# HK32L08x-EVAL.net
KiCad netlist of a schematic drawn in Altium Designer
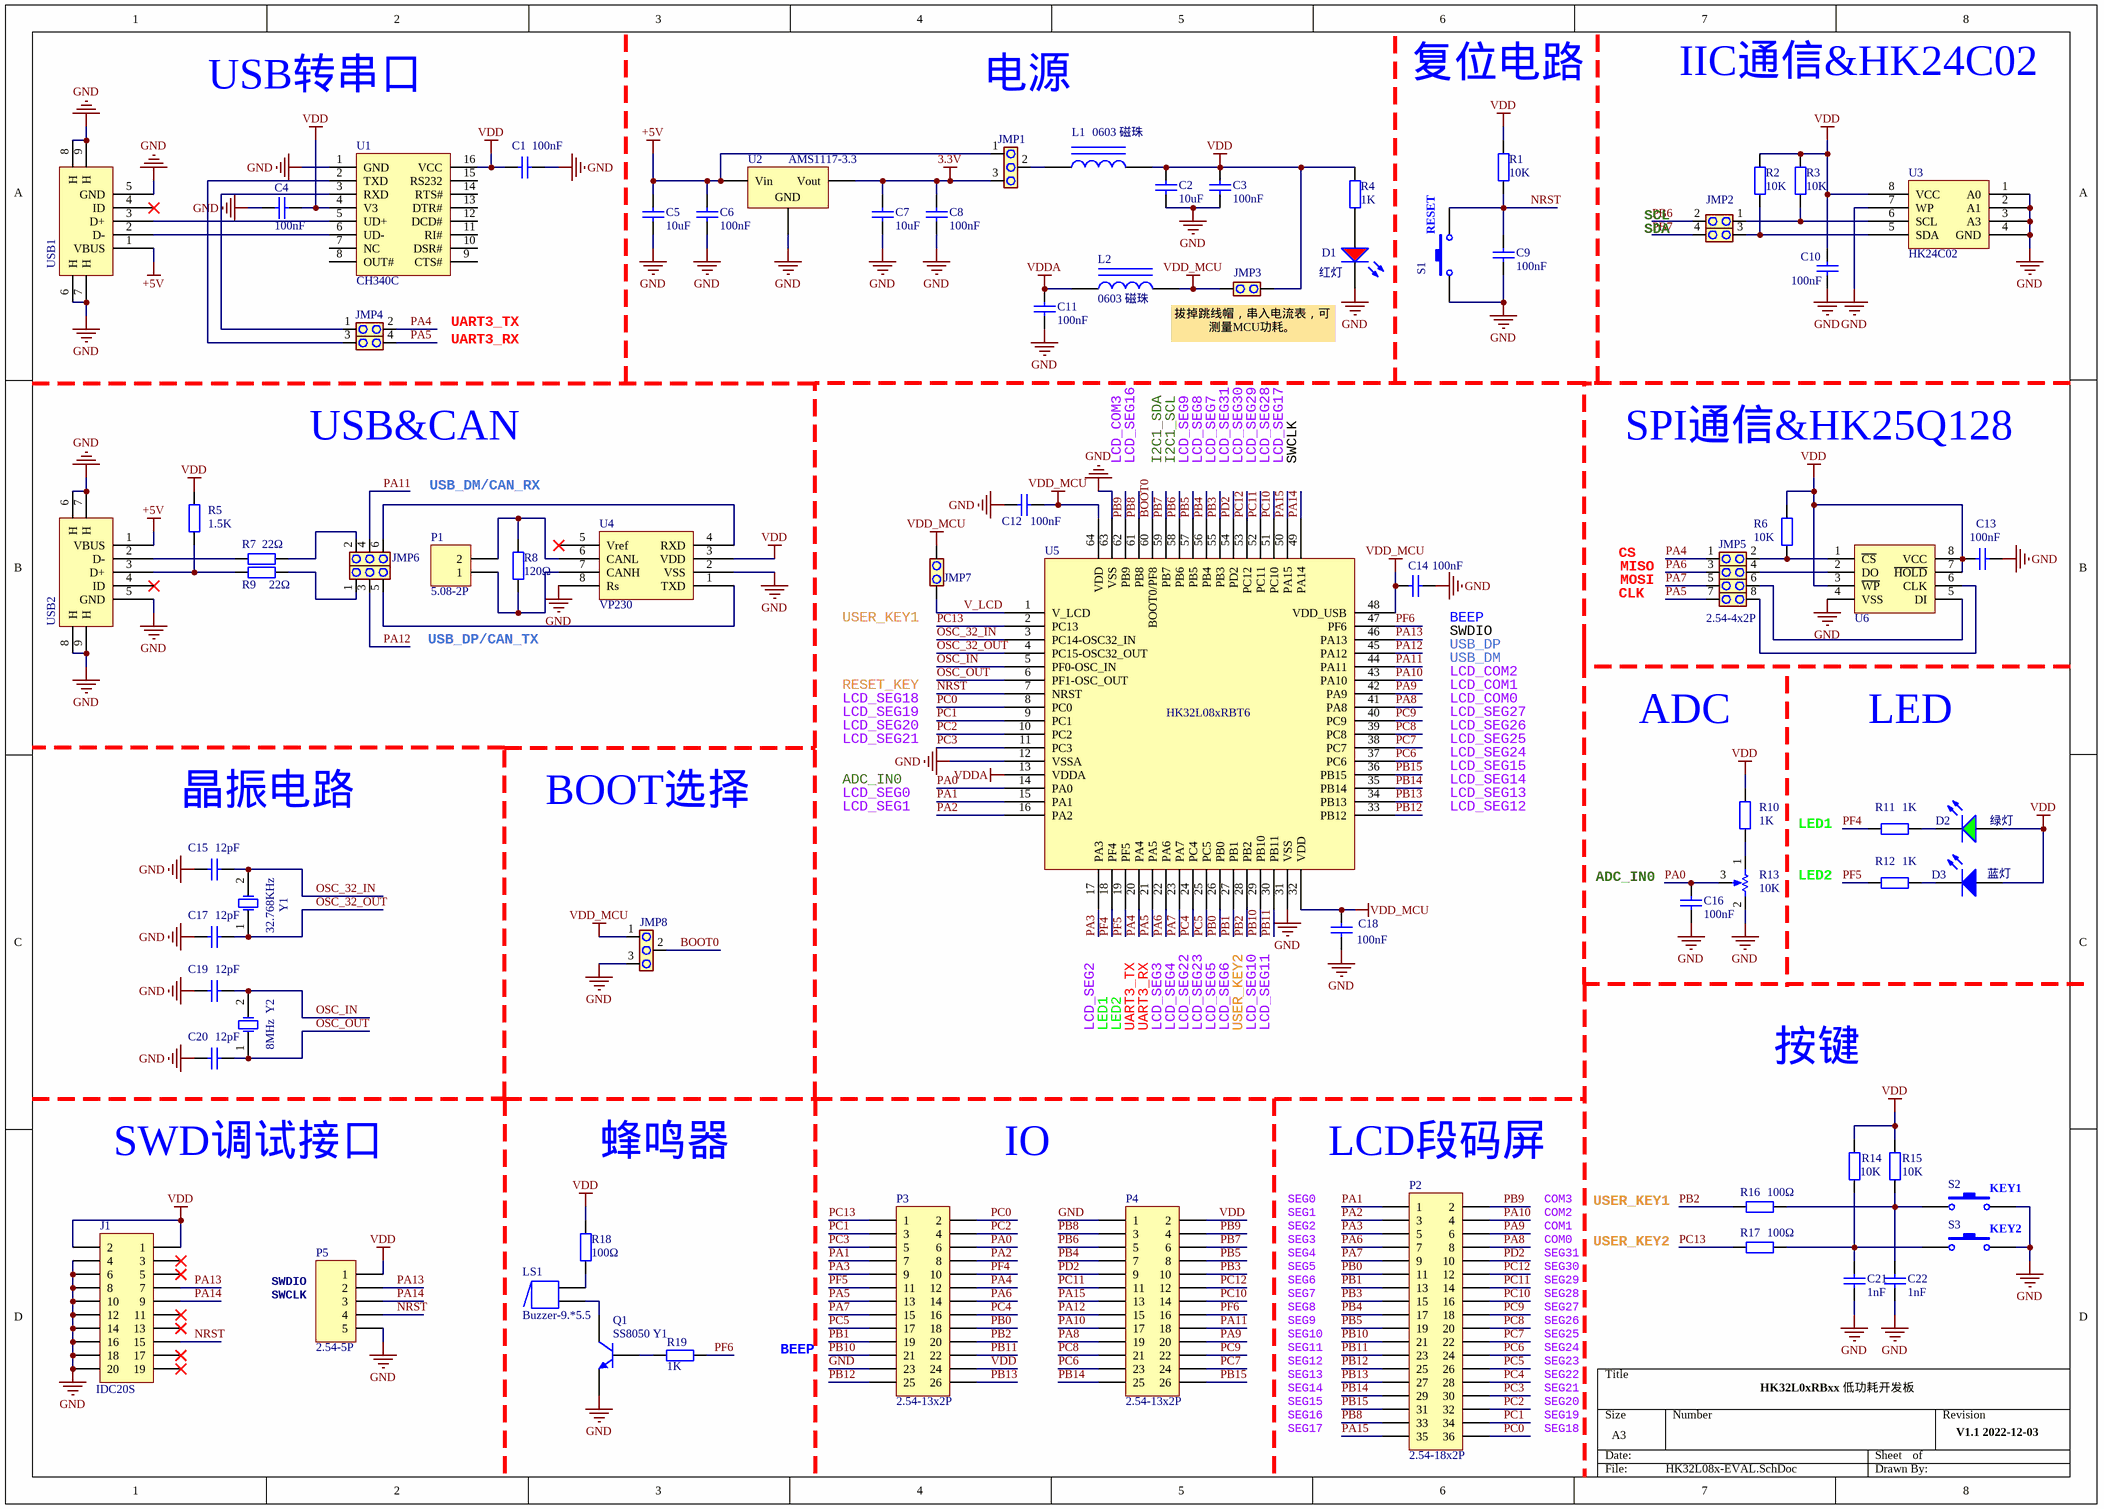
[diagram p0: HK32L08x-EVAL.SchDoc]

(export (version "E")
  (design (tool "Eeschema 10.0.6"))
  (components
    (comp (ref "C1")
      (value "100nF")
      (footprint "LC-0603_C")
      (description "贴片电容")
      (libsource (lib "Miscellaneous Devices LC") (part "0603 100nF (104) 10% 50V"))
    )
    (comp (ref "C2")
      (value "10uF")
      (footprint "LC-0603_C")
      (description "贴片电容")
      (libsource (lib "Miscellaneous Devices LC") (part "0603 10uF (106) 10% 10V"))
    )
    (comp (ref "C3")
      (value "100nF")
      (footprint "LC-0603_C")
      (description "贴片电容")
      (libsource (lib "Miscellaneous Devices LC") (part "0603 100nF (104) 10% 50V"))
    )
    (comp (ref "C4")
      (value "100nF")
      (footprint "LC-0603_C")
      (description "贴片电容")
      (libsource (lib "Miscellaneous Devices LC") (part "0603 100nF (104) 10% 50V"))
    )
    (comp (ref "C5")
      (value "10uF")
      (footprint "LC-1206_C")
      (description "贴片电容")
      (libsource (lib "Miscellaneous Devices LC") (part "1206 10uF (106) 10% 50V"))
    )
    (comp (ref "C6")
      (value "100nF")
      (footprint "LC-0603_C")
      (description "贴片电容")
      (libsource (lib "Miscellaneous Devices LC") (part "0603 100nF (104) 10% 50V"))
    )
    (comp (ref "C7")
      (value "10uF")
      (footprint "LC-1206_C")
      (description "贴片电容")
      (libsource (lib "Miscellaneous Devices LC") (part "1206 10uF (106) 10% 50V"))
    )
    (comp (ref "C8")
      (value "100nF")
      (footprint "LC-0603_C")
      (description "贴片电容")
      (libsource (lib "Miscellaneous Devices LC") (part "0603 100nF (104) 10% 50V"))
    )
    (comp (ref "C9")
      (value "100nF")
      (footprint "LC-0603_C")
      (description "贴片电容")
      (libsource (lib "Miscellaneous Devices LC") (part "0603 100nF (104) 10% 50V"))
    )
    (comp (ref "C10")
      (value "100nF")
      (footprint "LC-0603_C")
      (description "贴片电容")
      (libsource (lib "Miscellaneous Devices LC") (part "0603 100nF (104) 10% 50V"))
    )
    (comp (ref "C11")
      (value "100nF")
      (footprint "LC-0603_C")
      (description "贴片电容")
      (libsource (lib "Miscellaneous Devices LC") (part "0603 100nF (104) 10% 50V"))
    )
    (comp (ref "C12")
      (value "100nF")
      (footprint "LC-0603_C")
      (description "贴片电容")
      (libsource (lib "Miscellaneous Devices LC") (part "0603 100nF (104) 10% 50V"))
    )
    (comp (ref "C13")
      (value "100nF")
      (footprint "LC-0603_C")
      (description "贴片电容")
      (libsource (lib "Miscellaneous Devices LC") (part "0603 100nF (104) 10% 50V"))
    )
    (comp (ref "C14")
      (value "100nF")
      (footprint "LC-0603_C")
      (description "贴片电容")
      (libsource (lib "Miscellaneous Devices LC") (part "0603 100nF (104) 10% 50V"))
    )
    (comp (ref "C15")
      (value "12pF")
      (footprint "LC-0603_C")
      (description "贴片电容")
      (libsource (lib "Miscellaneous Devices LC") (part "0603 12pF (120) 5% 50V"))
    )
    (comp (ref "C16")
      (value "100nF")
      (footprint "LC-0603_C")
      (description "贴片电容")
      (libsource (lib "Miscellaneous Devices LC") (part "0603 100nF (104) 10% 50V"))
    )
    (comp (ref "C17")
      (value "12pF")
      (footprint "LC-0603_C")
      (description "贴片电容")
      (libsource (lib "Miscellaneous Devices LC") (part "0603 12pF (120) 5% 50V"))
    )
    (comp (ref "C18")
      (value "100nF")
      (footprint "LC-0603_C")
      (description "贴片电容")
      (libsource (lib "Miscellaneous Devices LC") (part "0603 100nF (104) 10% 50V"))
    )
    (comp (ref "C19")
      (value "12pF")
      (footprint "LC-0603_C")
      (description "贴片电容")
      (libsource (lib "Miscellaneous Devices LC") (part "0603 12pF (120) 5% 50V"))
    )
    (comp (ref "C20")
      (value "12pF")
      (footprint "LC-0603_C")
      (description "贴片电容")
      (libsource (lib "Miscellaneous Devices LC") (part "0603 12pF (120) 5% 50V"))
    )
    (comp (ref "C21")
      (value "1nF")
      (footprint "LC-0603_C")
      (description "贴片电容")
      (libsource (lib "Miscellaneous Devices LC") (part "0603 1nF (102) 10% 50V"))
    )
    (comp (ref "C22")
      (value "1nF")
      (footprint "LC-0603_C")
      (description "贴片电容")
      (libsource (lib "Miscellaneous Devices LC") (part "0603 1nF (102) 10% 50V"))
    )
    (comp (ref "D1")
      (value "红灯")
      (footprint "LC-0603_LED_S1")
      (description "贴片LED")
      (libsource (lib "Miscellaneous Devices LC") (part "0603 红灯"))
    )
    (comp (ref "D2")
      (value "绿灯")
      (footprint "LC-0603_LED_S1")
      (description "贴片LED")
      (libsource (lib "Miscellaneous Devices LC") (part "0603 绿灯"))
    )
    (comp (ref "D3")
      (value "蓝灯")
      (footprint "LC-0603_LED_S1")
      (description "贴片LED")
      (libsource (lib "Miscellaneous Devices LC") (part "0603 蓝灯"))
    )
    (comp (ref "J1")
      (value "IDC20S")
      (footprint "JTAG20P")
      (description "接插件")
      (fields (field (name "PUBLISHER") "Altium Limited"))
      (libsource (lib "Miscellaneous Connectors") (part "Header 10X2H"))
    )
    (comp (ref "JMP1")
      (value "2.54-3P")
      (footprint "HDR1X3")
      (description "排针")
      (libsource (lib "HK32L08x-EVAL") (part "JMP-3P"))
    )
    (comp (ref "JMP2")
      (value "2.54-2x2P")
      (footprint "HDR2X2")
      (description "排针")
      (libsource (lib "HK32L08x-EVAL") (part "JMP-2-2P"))
    )
    (comp (ref "JMP3")
      (value "2.54-2x1")
      (footprint "HDR1X2")
      (description "排针")
      (libsource (lib "HK32L08x-EVAL") (part "JMP-2P"))
    )
    (comp (ref "JMP4")
      (value "2.54-2x2P")
      (footprint "HDR2X2")
      (description "排针")
      (libsource (lib "") (part "JMP-2-2P_1"))
    )
    (comp (ref "JMP5")
      (value "2.54-4x2P")
      (footprint "HDR2X4")
      (description "排针")
      (libsource (lib "HK32L08x-EVAL") (part "JMP-2x4P"))
    )
    (comp (ref "JMP6")
      (value "2.54-3x2P")
      (footprint "HDR2X3")
      (description "排针")
      (libsource (lib "HK32L08x-EVAL") (part "JMP-2x3P"))
    )
    (comp (ref "JMP7")
      (value "2.54-2P")
      (footprint "HDR1X2")
      (description "排针")
      (libsource (lib "") (part "JMP-2P_1"))
    )
    (comp (ref "JMP8")
      (value "2.54-3P")
      (footprint "HDR1X3")
      (description "排针")
      (libsource (lib "HK32L08x-EVAL") (part "JMP-3P"))
    )
    (comp (ref "L1")
      (value "0603 磁珠")
      (footprint "LC-0603_L")
      (description "贴片电感")
      (libsource (lib "") (part "0603 10uH 10%_1"))
    )
    (comp (ref "L2")
      (value "0603 磁珠")
      (footprint "LC-0603_L")
      (description "贴片电感")
      (libsource (lib "Miscellaneous Devices LC") (part "0603 10uH 10%"))
    )
    (comp (ref "LS1")
      (value "Buzzer-9.*5.5")
      (footprint "Buzzer-2P-9x5.5")
      (description "直插蜂鸣器")
      (fields (field (name "PUBLISHER") "Altium Limited"))
      (libsource (lib "Miscellaneous Devices") (part "Buzzer"))
    )
    (comp (ref "P1")
      (value "5.08-2P")
      (footprint "HD-2PIN-5.08")
      (description "接插件")
      (fields (field (name "PUBLISHER") "Altium Limited"))
      (libsource (lib "Miscellaneous Connectors") (part "Header 2"))
    )
    (comp (ref "P2")
      (value "2.54-18x2P")
      (footprint "LCD128_2x18-2.54")
      (description "排母")
      (fields (field (name "PUBLISHER") "Altium Limited"))
      (libsource (lib "Miscellaneous Connectors") (part "Header 18X2"))
    )
    (comp (ref "P3")
      (value "2.54-13x2P")
      (footprint "HDR2X13")
      (description "排针")
      (fields (field (name "PUBLISHER") "Altium Limited"))
      (libsource (lib "Miscellaneous Connectors") (part "Header 13X2"))
    )
    (comp (ref "P4")
      (value "2.54-13x2P")
      (footprint "HDR2X13")
      (description "排针")
      (fields (field (name "PUBLISHER") "Altium Limited"))
      (libsource (lib "Miscellaneous Connectors") (part "Header 13X2"))
    )
    (comp (ref "P5")
      (value "2.54-5P")
      (footprint "HDR1X5")
      (description "排针")
      (fields (field (name "PUBLISHER") "Altium Limited"))
      (libsource (lib "Miscellaneous Connectors") (part "Header 5"))
    )
    (comp (ref "Q1")
      (value "SS8050 Y1")
      (footprint "LC-SOT-23(SOT-23-3)")
      (description "贴片三极管")
      (libsource (lib "Transistor_NPN") (part "SOT-23 SS8050 Y1"))
    )
    (comp (ref "R1")
      (value "10K")
      (footprint "LC-0603_R")
      (description "贴片电阻")
      (libsource (lib "") (part "0603 10KΩ (1002) 1%_1"))
    )
    (comp (ref "R2")
      (value "10K")
      (footprint "LC-0603_R")
      (description "贴片电阻")
      (libsource (lib "Miscellaneous Devices LC") (part "0603 10KΩ (1002) 1%"))
    )
    (comp (ref "R3")
      (value "10K")
      (footprint "LC-0603_R")
      (description "贴片电阻")
      (libsource (lib "Miscellaneous Devices LC") (part "0603 10KΩ (1002) 1%"))
    )
    (comp (ref "R4")
      (value "1K")
      (footprint "LC-0603_R")
      (description "贴片电阻")
      (libsource (lib "Miscellaneous Devices LC") (part "0603 1KΩ (1001) 1%"))
    )
    (comp (ref "R5")
      (value "1.5K")
      (footprint "LC-0603_R")
      (description "贴片电阻")
      (libsource (lib "Miscellaneous Devices LC") (part "0603 1.5KΩ (1501) 1%"))
    )
    (comp (ref "R6")
      (value "10K")
      (footprint "LC-0603_R")
      (description "贴片电阻")
      (libsource (lib "") (part "0603 10KΩ (1002) 1%_1"))
    )
    (comp (ref "R7")
      (value "22Ω")
      (footprint "LC-0603_R")
      (description "贴片电阻")
      (libsource (lib "Miscellaneous Devices LC") (part "0603 22Ω (22R0) 1%"))
    )
    (comp (ref "R8")
      (value "120Ω")
      (footprint "LC-0603_R")
      (description "贴片电阻")
      (libsource (lib "Miscellaneous Devices LC") (part "0603 120Ω (1200) 1%"))
    )
    (comp (ref "R9")
      (value "22Ω")
      (footprint "LC-0603_R")
      (description "贴片电阻")
      (libsource (lib "Miscellaneous Devices LC") (part "0603 22Ω (22R0) 1%"))
    )
    (comp (ref "R10")
      (value "1K")
      (footprint "LC-0603_R")
      (description "贴片电阻")
      (libsource (lib "Miscellaneous Devices LC") (part "0603 1KΩ (1001) 1%"))
    )
    (comp (ref "R11")
      (value "1K")
      (footprint "LC-0603_R")
      (description "贴片电阻")
      (libsource (lib "") (part "0603 1KΩ (1001) 1%_1"))
    )
    (comp (ref "R12")
      (value "1K")
      (footprint "LC-0603_R")
      (description "贴片电阻")
      (libsource (lib "") (part "0603 1KΩ (1001) 1%_1"))
    )
    (comp (ref "R13")
      (value "10K")
      (footprint "VR-3P")
      (description "直插电位器")
      (fields (field (name "Comment") "3386P-1") (field (name "PUBLISHER") "Altium Limited"))
      (libsource (lib "Miscellaneous Devices") (part "RPot"))
    )
    (comp (ref "R14")
      (value "10K")
      (footprint "LC-0603_R")
      (description "贴片电阻")
      (libsource (lib "") (part "0603 10KΩ (1002) 1%_1"))
    )
    (comp (ref "R15")
      (value "10K")
      (footprint "LC-0603_R")
      (description "贴片电阻")
      (libsource (lib "") (part "0603 10KΩ (1002) 1%_1"))
    )
    (comp (ref "R16")
      (value "100Ω")
      (footprint "LC-0603_R")
      (description "贴片电阻")
      (libsource (lib "Miscellaneous Devices LC") (part "0603 100Ω (1000) 1%"))
    )
    (comp (ref "R17")
      (value "100Ω")
      (footprint "LC-0603_R")
      (description "贴片电阻")
      (libsource (lib "Miscellaneous Devices LC") (part "0603 100Ω (1000) 1%"))
    )
    (comp (ref "R18")
      (value "100Ω")
      (footprint "LC-0603_R")
      (description "贴片电阻")
      (libsource (lib "Miscellaneous Devices LC") (part "0603 100Ω (1000) 1%"))
    )
    (comp (ref "R19")
      (value "1K")
      (footprint "LC-0603_R")
      (description "贴片电阻")
      (libsource (lib "") (part "0603 1KΩ (1001) 1%_2"))
    )
    (comp (ref "S1")
      (value "KEY-3*6*2.5")
      (footprint "SMD_KEY-2P")
      (description "贴片按键")
      (fields (field (name "PUBLISHER") "Altium Limited"))
      (libsource (lib "Miscellaneous Devices") (part "SW-PB"))
    )
    (comp (ref "S2")
      (value "KEY-3*6*2.5")
      (footprint "SMD_KEY-2P")
      (description "贴片按键")
      (fields (field (name "PUBLISHER") "Altium Limited"))
      (libsource (lib "Miscellaneous Devices") (part "SW-PB"))
    )
    (comp (ref "S3")
      (value "KEY-3*6*2.5")
      (footprint "SMD_KEY-2P")
      (description "贴片按键")
      (fields (field (name "PUBLISHER") "Altium Limited"))
      (libsource (lib "Miscellaneous Devices") (part "SW-PB"))
    )
    (comp (ref "U1")
      (value "CH340C")
      (footprint "LC-SOIC-16_150mil")
      (description "贴片IC")
      (libsource (lib "HK32L08x-EVAL") (part "CH340C"))
    )
    (comp (ref "U2")
      (value "AMS1117-3.3")
      (footprint "LC-SOT-223")
      (description "贴片IC")
      (libsource (lib "Miscellaneous Devices LC") (part "SOT-223 AMS1117-3.3"))
    )
    (comp (ref "U3")
      (value "HK24C02")
      (footprint "LC-SOIC-8_150mil")
      (description "贴片IC")
      (libsource (lib "IC") (part "EEPROM/AT24C256C-SSHL-T"))
    )
    (comp (ref "U4")
      (value "VP230")
      (footprint "LC-SOIC-8_150mil")
      (description "贴片IC")
      (libsource (lib "HK32L08x-EVAL") (part "VP230"))
    )
    (comp (ref "U5")
      (value "HK32L08xRBT6")
      (footprint "LC-LQFP-64_10x10x05P")
      (description "贴片IC")
      (libsource (lib "HK32L08x-EVAL") (part "HK32L08xRBT6"))
    )
    (comp (ref "U6")
      (value "HK25Q128")
      (footprint "FLASH-SOP8L")
      (description "贴片IC")
      (libsource (lib "HK32L08x-EVAL") (part "HK25Q128"))
    )
    (comp (ref "USB1")
      (value "MINI-USB")
      (footprint "mini_USB")
      (description "接插件")
      (libsource (lib "HK32L08x-EVAL") (part "MINI-USB"))
    )
    (comp (ref "USB2")
      (value "MINI-USB")
      (footprint "mini_USB")
      (description "接插件")
      (libsource (lib "") (part "MINI-USB_1"))
    )
    (comp (ref "Y1")
      (value "32.768KHz")
      (footprint "JZ32768")
      (description "直插晶振")
      (libsource (lib "Miscellaneous Devices LC") (part "SMD-3215_2P 32.768KHz 20ppm 12.5pF"))
    )
    (comp (ref "Y2")
      (value "8MHz")
      (footprint "JZ49S")
      (description "直插晶振")
      (libsource (lib "Miscellaneous Devices LC") (part "SMD-5032_2P 8MHz 20ppm 20pF"))
    )
  )
  (nets
    (net (code "1") (name "+5V") (class "Default")
      (node (ref "C5") (pin "2") (pinfunction "2_2") (pintype "passive"))
      (node (ref "C6") (pin "2") (pinfunction "2_2") (pintype "passive"))
      (node (ref "JMP1") (pin "1") (pinfunction "1_1") (pintype "passive"))
      (node (ref "U2") (pin "3") (pinfunction "Vin_3") (pintype "passive"))
      (node (ref "USB1") (pin "1") (pinfunction "VBUS_1") (pintype "passive"))
      (node (ref "USB2") (pin "1") (pinfunction "VBUS_1") (pintype "passive"))
    )
    (net (code "2") (name "/BOOT0") (class "Default")
      (node (ref "JMP8") (pin "2") (pinfunction "2_2") (pintype "passive"))
      (node (ref "U5") (pin "60") (pinfunction "BOOT0/PF8_60") (pintype "passive"))
    )
    (net (code "3") (name "/NRST") (class "Default")
      (node (ref "C9") (pin "2") (pinfunction "2_2") (pintype "passive"))
      (node (ref "J1") (pin "15") (pinfunction "15_15") (pintype "passive"))
      (node (ref "P5") (pin "4") (pinfunction "4_4") (pintype "passive"))
      (node (ref "R1") (pin "1") (pinfunction "1_1") (pintype "passive"))
      (node (ref "S1") (pin "2") (pinfunction "2_2") (pintype "passive"))
      (node (ref "U5") (pin "7") (pinfunction "NRST_7") (pintype "passive"))
    )
    (net (code "4") (name "/OSC_32_IN") (class "Default")
      (node (ref "C15") (pin "2") (pinfunction "2_2") (pintype "passive"))
      (node (ref "U5") (pin "3") (pinfunction "PC14-OSC32_IN_3") (pintype "passive"))
      (node (ref "Y1") (pin "2") (pinfunction "OSC2_2") (pintype "passive"))
    )
    (net (code "5") (name "/OSC_32_OUT") (class "Default")
      (node (ref "C17") (pin "2") (pinfunction "2_2") (pintype "passive"))
      (node (ref "U5") (pin "4") (pinfunction "PC15-OSC32_OUT_4") (pintype "passive"))
      (node (ref "Y1") (pin "1") (pinfunction "OSC1_1") (pintype "passive"))
    )
    (net (code "6") (name "/OSC_IN") (class "Default")
      (node (ref "C19") (pin "2") (pinfunction "2_2") (pintype "passive"))
      (node (ref "U5") (pin "5") (pinfunction "PF0-OSC_IN_5") (pintype "passive"))
      (node (ref "Y2") (pin "2") (pinfunction "OSC2_2") (pintype "passive"))
    )
    (net (code "7") (name "/OSC_OUT") (class "Default")
      (node (ref "C20") (pin "2") (pinfunction "2_2") (pintype "passive"))
      (node (ref "U5") (pin "6") (pinfunction "PF1-OSC_OUT_6") (pintype "passive"))
      (node (ref "Y2") (pin "1") (pinfunction "OSC1_1") (pintype "passive"))
    )
    (net (code "8") (name "/PA0") (class "Default")
      (node (ref "C16") (pin "1") (pinfunction "1_1") (pintype "passive"))
      (node (ref "P3") (pin "6") (pinfunction "6_6") (pintype "passive"))
      (node (ref "R13") (pin "3") (pinfunction "TAP_3") (pintype "passive"))
      (node (ref "U5") (pin "14") (pinfunction "PA0_14") (pintype "passive"))
    )
    (net (code "9") (name "/PA1") (class "Default")
      (node (ref "P2") (pin "1") (pinfunction "1_1") (pintype "passive"))
      (node (ref "P3") (pin "7") (pinfunction "7_7") (pintype "passive"))
      (node (ref "U5") (pin "15") (pinfunction "PA1_15") (pintype "passive"))
    )
    (net (code "10") (name "/PA2") (class "Default")
      (node (ref "P2") (pin "3") (pinfunction "3_3") (pintype "passive"))
      (node (ref "P3") (pin "8") (pinfunction "8_8") (pintype "passive"))
      (node (ref "U5") (pin "16") (pinfunction "PA2_16") (pintype "passive"))
    )
    (net (code "11") (name "/PA3") (class "Default")
      (node (ref "P2") (pin "5") (pinfunction "5_5") (pintype "passive"))
      (node (ref "P3") (pin "9") (pinfunction "9_9") (pintype "passive"))
      (node (ref "U5") (pin "17") (pinfunction "PA3_17") (pintype "passive"))
    )
    (net (code "12") (name "/PA4") (class "Default")
      (node (ref "JMP4") (pin "2") (pinfunction "2_2") (pintype "passive"))
      (node (ref "JMP5") (pin "1") (pinfunction "1_1") (pintype "passive"))
      (node (ref "P3") (pin "12") (pinfunction "12_12") (pintype "passive"))
      (node (ref "U5") (pin "20") (pinfunction "PA4_20") (pintype "passive"))
    )
    (net (code "13") (name "/PA5") (class "Default")
      (node (ref "JMP4") (pin "4") (pinfunction "4_4") (pintype "passive"))
      (node (ref "JMP5") (pin "7") (pinfunction "7_7") (pintype "passive"))
      (node (ref "P3") (pin "13") (pinfunction "13_13") (pintype "passive"))
      (node (ref "U5") (pin "21") (pinfunction "PA5_21") (pintype "passive"))
    )
    (net (code "14") (name "/PA6") (class "Default")
      (node (ref "JMP5") (pin "3") (pinfunction "3_3") (pintype "passive"))
      (node (ref "P2") (pin "7") (pinfunction "7_7") (pintype "passive"))
      (node (ref "P3") (pin "14") (pinfunction "14_14") (pintype "passive"))
      (node (ref "U5") (pin "22") (pinfunction "PA6_22") (pintype "passive"))
    )
    (net (code "15") (name "/PA7") (class "Default")
      (node (ref "JMP5") (pin "5") (pinfunction "5_5") (pintype "passive"))
      (node (ref "P2") (pin "9") (pinfunction "9_9") (pintype "passive"))
      (node (ref "P3") (pin "15") (pinfunction "15_15") (pintype "passive"))
      (node (ref "U5") (pin "23") (pinfunction "PA7_23") (pintype "passive"))
    )
    (net (code "16") (name "/PA8") (class "Default")
      (node (ref "P2") (pin "8") (pinfunction "8_8") (pintype "passive"))
      (node (ref "P4") (pin "19") (pinfunction "19_19") (pintype "passive"))
      (node (ref "U5") (pin "41") (pinfunction "PA8_41") (pintype "passive"))
    )
    (net (code "17") (name "/PA9") (class "Default")
      (node (ref "P2") (pin "6") (pinfunction "6_6") (pintype "passive"))
      (node (ref "P4") (pin "20") (pinfunction "20_20") (pintype "passive"))
      (node (ref "U5") (pin "42") (pinfunction "PA9_42") (pintype "passive"))
    )
    (net (code "18") (name "/PA10") (class "Default")
      (node (ref "P2") (pin "4") (pinfunction "4_4") (pintype "passive"))
      (node (ref "P4") (pin "17") (pinfunction "17_17") (pintype "passive"))
      (node (ref "U5") (pin "43") (pinfunction "PA10_43") (pintype "passive"))
    )
    (net (code "19") (name "/PA11") (class "Default")
      (node (ref "JMP6") (pin "4") (pinfunction "4_4") (pintype "passive"))
      (node (ref "P4") (pin "18") (pinfunction "18_18") (pintype "passive"))
      (node (ref "U5") (pin "44") (pinfunction "PA11_44") (pintype "passive"))
    )
    (net (code "20") (name "/PA12") (class "Default")
      (node (ref "JMP6") (pin "3") (pinfunction "3_3") (pintype "passive"))
      (node (ref "P4") (pin "15") (pinfunction "15_15") (pintype "passive"))
      (node (ref "U5") (pin "45") (pinfunction "PA12_45") (pintype "passive"))
    )
    (net (code "21") (name "/PA13") (class "Default")
      (node (ref "J1") (pin "7") (pinfunction "7_7") (pintype "passive"))
      (node (ref "P5") (pin "2") (pinfunction "2_2") (pintype "passive"))
      (node (ref "U5") (pin "46") (pinfunction "PA13_46") (pintype "passive"))
    )
    (net (code "22") (name "/PA14") (class "Default")
      (node (ref "J1") (pin "9") (pinfunction "9_9") (pintype "passive"))
      (node (ref "P5") (pin "3") (pinfunction "3_3") (pintype "passive"))
      (node (ref "U5") (pin "49") (pinfunction "PA14_49") (pintype "passive"))
    )
    (net (code "23") (name "/PA15") (class "Default")
      (node (ref "P2") (pin "35") (pinfunction "35_35") (pintype "passive"))
      (node (ref "P4") (pin "13") (pinfunction "13_13") (pintype "passive"))
      (node (ref "U5") (pin "50") (pinfunction "PA15_50") (pintype "passive"))
    )
    (net (code "24") (name "/PB0") (class "Default")
      (node (ref "P2") (pin "11") (pinfunction "11_11") (pintype "passive"))
      (node (ref "P3") (pin "18") (pinfunction "18_18") (pintype "passive"))
      (node (ref "U5") (pin "26") (pinfunction "PB0_26") (pintype "passive"))
    )
    (net (code "25") (name "/PB1") (class "Default")
      (node (ref "P2") (pin "13") (pinfunction "13_13") (pintype "passive"))
      (node (ref "P3") (pin "19") (pinfunction "19_19") (pintype "passive"))
      (node (ref "U5") (pin "27") (pinfunction "PB1_27") (pintype "passive"))
    )
    (net (code "26") (name "/PB2") (class "Default")
      (node (ref "P3") (pin "20") (pinfunction "20_20") (pintype "passive"))
      (node (ref "R16") (pin "1") (pinfunction "1_1") (pintype "passive"))
      (node (ref "U5") (pin "28") (pinfunction "PB2_28") (pintype "passive"))
    )
    (net (code "27") (name "/PB3") (class "Default")
      (node (ref "P2") (pin "15") (pinfunction "15_15") (pintype "passive"))
      (node (ref "P4") (pin "10") (pinfunction "10_10") (pintype "passive"))
      (node (ref "U5") (pin "55") (pinfunction "PB3_55") (pintype "passive"))
    )
    (net (code "28") (name "/PB4") (class "Default")
      (node (ref "P2") (pin "17") (pinfunction "17_17") (pintype "passive"))
      (node (ref "P4") (pin "7") (pinfunction "7_7") (pintype "passive"))
      (node (ref "U5") (pin "56") (pinfunction "PB4_56") (pintype "passive"))
    )
    (net (code "29") (name "/PB5") (class "Default")
      (node (ref "P2") (pin "19") (pinfunction "19_19") (pintype "passive"))
      (node (ref "P4") (pin "8") (pinfunction "8_8") (pintype "passive"))
      (node (ref "U5") (pin "57") (pinfunction "PB5_57") (pintype "passive"))
    )
    (net (code "30") (name "/PB6") (class "Default")
      (node (ref "JMP2") (pin "2") (pinfunction "2_2") (pintype "passive"))
      (node (ref "P4") (pin "5") (pinfunction "5_5") (pintype "passive"))
      (node (ref "U5") (pin "58") (pinfunction "PB6_58") (pintype "passive"))
    )
    (net (code "31") (name "/PB7") (class "Default")
      (node (ref "JMP2") (pin "4") (pinfunction "4_4") (pintype "passive"))
      (node (ref "P4") (pin "6") (pinfunction "6_6") (pintype "passive"))
      (node (ref "U5") (pin "59") (pinfunction "PB7_59") (pintype "passive"))
    )
    (net (code "32") (name "/PB8") (class "Default")
      (node (ref "P2") (pin "33") (pinfunction "33_33") (pintype "passive"))
      (node (ref "P4") (pin "3") (pinfunction "3_3") (pintype "passive"))
      (node (ref "U5") (pin "61") (pinfunction "PB8_61") (pintype "passive"))
    )
    (net (code "33") (name "/PB9") (class "Default")
      (node (ref "P2") (pin "2") (pinfunction "2_2") (pintype "passive"))
      (node (ref "P4") (pin "4") (pinfunction "4_4") (pintype "passive"))
      (node (ref "U5") (pin "62") (pinfunction "PB9_62") (pintype "passive"))
    )
    (net (code "34") (name "/PB10") (class "Default")
      (node (ref "P2") (pin "21") (pinfunction "21_21") (pintype "passive"))
      (node (ref "P3") (pin "21") (pinfunction "21_21") (pintype "passive"))
      (node (ref "U5") (pin "29") (pinfunction "PB10_29") (pintype "passive"))
    )
    (net (code "35") (name "/PB11") (class "Default")
      (node (ref "P2") (pin "23") (pinfunction "23_23") (pintype "passive"))
      (node (ref "P3") (pin "22") (pinfunction "22_22") (pintype "passive"))
      (node (ref "U5") (pin "30") (pinfunction "PB11_30") (pintype "passive"))
    )
    (net (code "36") (name "/PB12") (class "Default")
      (node (ref "P2") (pin "25") (pinfunction "25_25") (pintype "passive"))
      (node (ref "P3") (pin "25") (pinfunction "25_25") (pintype "passive"))
      (node (ref "U5") (pin "33") (pinfunction "PB12_33") (pintype "passive"))
    )
    (net (code "37") (name "/PB13") (class "Default")
      (node (ref "P2") (pin "27") (pinfunction "27_27") (pintype "passive"))
      (node (ref "P3") (pin "26") (pinfunction "26_26") (pintype "passive"))
      (node (ref "U5") (pin "34") (pinfunction "PB13_34") (pintype "passive"))
    )
    (net (code "38") (name "/PB14") (class "Default")
      (node (ref "P2") (pin "29") (pinfunction "29_29") (pintype "passive"))
      (node (ref "P4") (pin "25") (pinfunction "25_25") (pintype "passive"))
      (node (ref "U5") (pin "35") (pinfunction "PB14_35") (pintype "passive"))
    )
    (net (code "39") (name "/PB15") (class "Default")
      (node (ref "P2") (pin "31") (pinfunction "31_31") (pintype "passive"))
      (node (ref "P4") (pin "26") (pinfunction "26_26") (pintype "passive"))
      (node (ref "U5") (pin "36") (pinfunction "PB15_36") (pintype "passive"))
    )
    (net (code "40") (name "/PC0") (class "Default")
      (node (ref "P2") (pin "36") (pinfunction "36_36") (pintype "passive"))
      (node (ref "P3") (pin "2") (pinfunction "2_2") (pintype "passive"))
      (node (ref "U5") (pin "8") (pinfunction "PC0_8") (pintype "passive"))
    )
    (net (code "41") (name "/PC1") (class "Default")
      (node (ref "P2") (pin "34") (pinfunction "34_34") (pintype "passive"))
      (node (ref "P3") (pin "3") (pinfunction "3_3") (pintype "passive"))
      (node (ref "U5") (pin "9") (pinfunction "PC1_9") (pintype "passive"))
    )
    (net (code "42") (name "/PC2") (class "Default")
      (node (ref "P2") (pin "32") (pinfunction "32_32") (pintype "passive"))
      (node (ref "P3") (pin "4") (pinfunction "4_4") (pintype "passive"))
      (node (ref "U5") (pin "10") (pinfunction "PC2_10") (pintype "passive"))
    )
    (net (code "43") (name "/PC3") (class "Default")
      (node (ref "P2") (pin "30") (pinfunction "30_30") (pintype "passive"))
      (node (ref "P3") (pin "5") (pinfunction "5_5") (pintype "passive"))
      (node (ref "U5") (pin "11") (pinfunction "PC3_11") (pintype "passive"))
    )
    (net (code "44") (name "/PC4") (class "Default")
      (node (ref "P2") (pin "28") (pinfunction "28_28") (pintype "passive"))
      (node (ref "P3") (pin "16") (pinfunction "16_16") (pintype "passive"))
      (node (ref "U5") (pin "24") (pinfunction "PC4_24") (pintype "passive"))
    )
    (net (code "45") (name "/PC5") (class "Default")
      (node (ref "P2") (pin "26") (pinfunction "26_26") (pintype "passive"))
      (node (ref "P3") (pin "17") (pinfunction "17_17") (pintype "passive"))
      (node (ref "U5") (pin "25") (pinfunction "PC5_25") (pintype "passive"))
    )
    (net (code "46") (name "/PC6") (class "Default")
      (node (ref "P2") (pin "24") (pinfunction "24_24") (pintype "passive"))
      (node (ref "P4") (pin "23") (pinfunction "23_23") (pintype "passive"))
      (node (ref "U5") (pin "37") (pinfunction "PC6_37") (pintype "passive"))
    )
    (net (code "47") (name "/PC7") (class "Default")
      (node (ref "P2") (pin "22") (pinfunction "22_22") (pintype "passive"))
      (node (ref "P4") (pin "24") (pinfunction "24_24") (pintype "passive"))
      (node (ref "U5") (pin "38") (pinfunction "PC7_38") (pintype "passive"))
    )
    (net (code "48") (name "/PC8") (class "Default")
      (node (ref "P2") (pin "20") (pinfunction "20_20") (pintype "passive"))
      (node (ref "P4") (pin "21") (pinfunction "21_21") (pintype "passive"))
      (node (ref "U5") (pin "39") (pinfunction "PC8_39") (pintype "passive"))
    )
    (net (code "49") (name "/PC9") (class "Default")
      (node (ref "P2") (pin "18") (pinfunction "18_18") (pintype "passive"))
      (node (ref "P4") (pin "22") (pinfunction "22_22") (pintype "passive"))
      (node (ref "U5") (pin "40") (pinfunction "PC9_40") (pintype "passive"))
    )
    (net (code "50") (name "/PC10") (class "Default")
      (node (ref "P2") (pin "16") (pinfunction "16_16") (pintype "passive"))
      (node (ref "P4") (pin "14") (pinfunction "14_14") (pintype "passive"))
      (node (ref "U5") (pin "51") (pinfunction "PC10_51") (pintype "passive"))
    )
    (net (code "51") (name "/PC11") (class "Default")
      (node (ref "P2") (pin "14") (pinfunction "14_14") (pintype "passive"))
      (node (ref "P4") (pin "11") (pinfunction "11_11") (pintype "passive"))
      (node (ref "U5") (pin "52") (pinfunction "PC11_52") (pintype "passive"))
    )
    (net (code "52") (name "/PC12") (class "Default")
      (node (ref "P2") (pin "12") (pinfunction "12_12") (pintype "passive"))
      (node (ref "P4") (pin "12") (pinfunction "12_12") (pintype "passive"))
      (node (ref "U5") (pin "53") (pinfunction "PC12_53") (pintype "passive"))
    )
    (net (code "53") (name "/PC13") (class "Default")
      (node (ref "P3") (pin "1") (pinfunction "1_1") (pintype "passive"))
      (node (ref "R17") (pin "1") (pinfunction "1_1") (pintype "passive"))
      (node (ref "U5") (pin "2") (pinfunction "PC13_2") (pintype "passive"))
    )
    (net (code "54") (name "/PD2") (class "Default")
      (node (ref "P2") (pin "10") (pinfunction "10_10") (pintype "passive"))
      (node (ref "P4") (pin "9") (pinfunction "9_9") (pintype "passive"))
      (node (ref "U5") (pin "54") (pinfunction "PD2_54") (pintype "passive"))
    )
    (net (code "55") (name "/PF4") (class "Default")
      (node (ref "P3") (pin "10") (pinfunction "10_10") (pintype "passive"))
      (node (ref "R11") (pin "2") (pinfunction "2_2") (pintype "passive"))
      (node (ref "U5") (pin "18") (pinfunction "PF4_18") (pintype "passive"))
    )
    (net (code "56") (name "/PF5") (class "Default")
      (node (ref "P3") (pin "11") (pinfunction "11_11") (pintype "passive"))
      (node (ref "R12") (pin "2") (pinfunction "2_2") (pintype "passive"))
      (node (ref "U5") (pin "19") (pinfunction "PF5_19") (pintype "passive"))
    )
    (net (code "57") (name "/PF6") (class "Default")
      (node (ref "P4") (pin "16") (pinfunction "16_16") (pintype "passive"))
      (node (ref "R19") (pin "1") (pinfunction "1_1") (pintype "passive"))
      (node (ref "U5") (pin "47") (pinfunction "PF6_47") (pintype "passive"))
    )
    (net (code "58") (name "/V_LCD") (class "Default")
      (node (ref "JMP7") (pin "2") (pinfunction "2_2") (pintype "passive"))
      (node (ref "U5") (pin "1") (pinfunction "V_LCD_1") (pintype "passive"))
    )
    (net (code "59") (name "3.3V") (class "Default")
      (node (ref "C7") (pin "2") (pinfunction "2_2") (pintype "passive"))
      (node (ref "C8") (pin "2") (pinfunction "2_2") (pintype "passive"))
      (node (ref "JMP1") (pin "3") (pinfunction "3_3") (pintype "passive"))
      (node (ref "U2") (pin "2") (pinfunction "Vout_2") (pintype "passive"))
    )
    (net (code "60") (name "GND") (class "Default")
      (node (ref "C1") (pin "1") (pinfunction "1_1") (pintype "passive"))
      (node (ref "C10") (pin "1") (pinfunction "1_1") (pintype "passive"))
      (node (ref "C11") (pin "1") (pinfunction "1_1") (pintype "passive"))
      (node (ref "C12") (pin "2") (pinfunction "2_2") (pintype "passive"))
      (node (ref "C13") (pin "1") (pinfunction "1_1") (pintype "passive"))
      (node (ref "C14") (pin "2") (pinfunction "2_2") (pintype "passive"))
      (node (ref "C15") (pin "1") (pinfunction "1_1") (pintype "passive"))
      (node (ref "C16") (pin "2") (pinfunction "2_2") (pintype "passive"))
      (node (ref "C17") (pin "1") (pinfunction "1_1") (pintype "passive"))
      (node (ref "C18") (pin "2") (pinfunction "2_2") (pintype "passive"))
      (node (ref "C19") (pin "1") (pinfunction "1_1") (pintype "passive"))
      (node (ref "C2") (pin "1") (pinfunction "1_1") (pintype "passive"))
      (node (ref "C20") (pin "1") (pinfunction "1_1") (pintype "passive"))
      (node (ref "C21") (pin "1") (pinfunction "1_1") (pintype "passive"))
      (node (ref "C22") (pin "1") (pinfunction "1_1") (pintype "passive"))
      (node (ref "C3") (pin "1") (pinfunction "1_1") (pintype "passive"))
      (node (ref "C4") (pin "2") (pinfunction "2_2") (pintype "passive"))
      (node (ref "C5") (pin "1") (pinfunction "1_1") (pintype "passive"))
      (node (ref "C6") (pin "1") (pinfunction "1_1") (pintype "passive"))
      (node (ref "C7") (pin "1") (pinfunction "1_1") (pintype "passive"))
      (node (ref "C8") (pin "1") (pinfunction "1_1") (pintype "passive"))
      (node (ref "C9") (pin "1") (pinfunction "1_1") (pintype "passive"))
      (node (ref "D1") (pin "K") (pinfunction "K_K") (pintype "passive"))
      (node (ref "J1") (pin "10") (pinfunction "10_10") (pintype "passive"))
      (node (ref "J1") (pin "12") (pinfunction "12_12") (pintype "passive"))
      (node (ref "J1") (pin "14") (pinfunction "14_14") (pintype "passive"))
      (node (ref "J1") (pin "16") (pinfunction "16_16") (pintype "passive"))
      (node (ref "J1") (pin "18") (pinfunction "18_18") (pintype "passive"))
      (node (ref "J1") (pin "20") (pinfunction "20_20") (pintype "passive"))
      (node (ref "J1") (pin "4") (pinfunction "4_4") (pintype "passive"))
      (node (ref "J1") (pin "6") (pinfunction "6_6") (pintype "passive"))
      (node (ref "J1") (pin "8") (pinfunction "8_8") (pintype "passive"))
      (node (ref "JMP8") (pin "3") (pinfunction "3_3") (pintype "passive"))
      (node (ref "P3") (pin "23") (pinfunction "23_23") (pintype "passive"))
      (node (ref "P4") (pin "1") (pinfunction "1_1") (pintype "passive"))
      (node (ref "P5") (pin "5") (pinfunction "5_5") (pintype "passive"))
      (node (ref "Q1") (pin "2") (pinfunction "E_2") (pintype "passive"))
      (node (ref "R13") (pin "2") (pinfunction "BOT_2") (pintype "passive"))
      (node (ref "S1") (pin "1") (pinfunction "1_1") (pintype "passive"))
      (node (ref "S2") (pin "2") (pinfunction "2_2") (pintype "passive"))
      (node (ref "S3") (pin "2") (pinfunction "2_2") (pintype "passive"))
      (node (ref "U1") (pin "1") (pinfunction "GND_1") (pintype "passive"))
      (node (ref "U2") (pin "1") (pinfunction "GND_1") (pintype "passive"))
      (node (ref "U3") (pin "1") (pinfunction "A0_1") (pintype "passive"))
      (node (ref "U3") (pin "2") (pinfunction "A1_2") (pintype "passive"))
      (node (ref "U3") (pin "3") (pinfunction "A3_3") (pintype "passive"))
      (node (ref "U3") (pin "4") (pinfunction "GND_4") (pintype "passive"))
      (node (ref "U3") (pin "7") (pinfunction "WP_7") (pintype "passive"))
      (node (ref "U4") (pin "2") (pinfunction "VSS_2") (pintype "passive"))
      (node (ref "U4") (pin "8") (pinfunction "Rs_8") (pintype "passive"))
      (node (ref "U5") (pin "12") (pinfunction "VSSA_12") (pintype "passive"))
      (node (ref "U5") (pin "31") (pinfunction "VSS_31") (pintype "passive"))
      (node (ref "U5") (pin "63") (pinfunction "VSS_63") (pintype "passive"))
      (node (ref "U6") (pin "4") (pinfunction "VSS_4") (pintype "passive"))
      (node (ref "USB1") (pin "5") (pinfunction "GND_5") (pintype "passive"))
      (node (ref "USB1") (pin "6") (pinfunction "H_6") (pintype "passive"))
      (node (ref "USB1") (pin "7") (pinfunction "H_7") (pintype "passive"))
      (node (ref "USB1") (pin "8") (pinfunction "H_8") (pintype "passive"))
      (node (ref "USB1") (pin "9") (pinfunction "H_9") (pintype "passive"))
      (node (ref "USB2") (pin "5") (pinfunction "GND_5") (pintype "passive"))
      (node (ref "USB2") (pin "6") (pinfunction "H_6") (pintype "passive"))
      (node (ref "USB2") (pin "7") (pinfunction "H_7") (pintype "passive"))
      (node (ref "USB2") (pin "8") (pinfunction "H_8") (pintype "passive"))
      (node (ref "USB2") (pin "9") (pinfunction "H_9") (pintype "passive"))
    )
    (net (code "61") (name "Net-(C21-Pad2)") (class "Default")
      (node (ref "C21") (pin "2") (pinfunction "2_2") (pintype "passive"))
      (node (ref "R14") (pin "1") (pinfunction "1_1") (pintype "passive"))
      (node (ref "R17") (pin "2") (pinfunction "2_2") (pintype "passive"))
      (node (ref "S3") (pin "1") (pinfunction "1_1") (pintype "passive"))
    )
    (net (code "62") (name "Net-(C22-Pad2)") (class "Default")
      (node (ref "C22") (pin "2") (pinfunction "2_2") (pintype "passive"))
      (node (ref "R15") (pin "1") (pinfunction "1_1") (pintype "passive"))
      (node (ref "R16") (pin "2") (pinfunction "2_2") (pintype "passive"))
      (node (ref "S2") (pin "1") (pinfunction "1_1") (pintype "passive"))
    )
    (net (code "63") (name "Net-(D1-PadA)") (class "Default")
      (node (ref "D1") (pin "A") (pinfunction "A_A") (pintype "passive"))
      (node (ref "R4") (pin "1") (pinfunction "1_1") (pintype "passive"))
    )
    (net (code "64") (name "Net-(D2-PadK)") (class "Default")
      (node (ref "D2") (pin "K") (pinfunction "K_K") (pintype "passive"))
      (node (ref "R11") (pin "1") (pinfunction "1_1") (pintype "passive"))
    )
    (net (code "65") (name "Net-(D3-PadK)") (class "Default")
      (node (ref "D3") (pin "K") (pinfunction "K_K") (pintype "passive"))
      (node (ref "R12") (pin "1") (pinfunction "1_1") (pintype "passive"))
    )
    (net (code "66") (name "Net-(JMP1-Pad2)") (class "Default")
      (node (ref "JMP1") (pin "2") (pinfunction "2_2") (pintype "passive"))
      (node (ref "L1") (pin "1") (pinfunction "1_1") (pintype "passive"))
    )
    (net (code "67") (name "Net-(JMP6-Pad1)") (class "Default")
      (node (ref "JMP6") (pin "1") (pinfunction "1_1") (pintype "passive"))
      (node (ref "R9") (pin "2") (pinfunction "2_2") (pintype "passive"))
    )
    (net (code "68") (name "Net-(JMP6-Pad2)") (class "Default")
      (node (ref "JMP6") (pin "2") (pinfunction "2_2") (pintype "passive"))
      (node (ref "R7") (pin "2") (pinfunction "2_2") (pintype "passive"))
    )
    (net (code "69") (name "Net-(LS1-Pad1)") (class "Default")
      (node (ref "LS1") (pin "1") (pinfunction "1_1") (pintype "passive"))
      (node (ref "R18") (pin "1") (pinfunction "1_1") (pintype "passive"))
    )
    (net (code "70") (name "Net-(Q1-B)") (class "Default")
      (node (ref "Q1") (pin "1") (pinfunction "B_1") (pintype "passive"))
      (node (ref "R19") (pin "2") (pinfunction "2_2") (pintype "passive"))
    )
    (net (code "71") (name "Net-(Q1-C)") (class "Default")
      (node (ref "LS1") (pin "2") (pinfunction "2_2") (pintype "passive"))
      (node (ref "Q1") (pin "3") (pinfunction "C_3") (pintype "passive"))
    )
    (net (code "72") (name "Net-(R13-TOP)") (class "Default")
      (node (ref "R10") (pin "1") (pinfunction "1_1") (pintype "passive"))
      (node (ref "R13") (pin "1") (pinfunction "TOP_1") (pintype "passive"))
    )
    (net (code "73") (name "Net-(U1-RXD)") (class "Default")
      (node (ref "JMP4") (pin "1") (pinfunction "1_1") (pintype "passive"))
      (node (ref "U1") (pin "3") (pinfunction "RXD_3") (pintype "passive"))
    )
    (net (code "74") (name "Net-(U1-TXD)") (class "Default")
      (node (ref "JMP4") (pin "3") (pinfunction "3_3") (pintype "passive"))
      (node (ref "U1") (pin "2") (pinfunction "TXD_2") (pintype "passive"))
    )
    (net (code "75") (name "Net-(U1-UD+)") (class "Default")
      (node (ref "U1") (pin "5") (pinfunction "UD+_5") (pintype "passive"))
      (node (ref "USB1") (pin "3") (pinfunction "D+_3") (pintype "passive"))
    )
    (net (code "76") (name "Net-(U1-UD-)") (class "Default")
      (node (ref "U1") (pin "6") (pinfunction "UD-_6") (pintype "passive"))
      (node (ref "USB1") (pin "2") (pinfunction "D-_2") (pintype "passive"))
    )
    (net (code "77") (name "Net-(U3-SCL)") (class "Default")
      (node (ref "JMP2") (pin "1") (pinfunction "1_1") (pintype "passive"))
      (node (ref "R3") (pin "1") (pinfunction "1_1") (pintype "passive"))
      (node (ref "U3") (pin "6") (pinfunction "SCL_6") (pintype "passive"))
    )
    (net (code "78") (name "Net-(U3-SDA)") (class "Default")
      (node (ref "JMP2") (pin "3") (pinfunction "3_3") (pintype "passive"))
      (node (ref "R2") (pin "1") (pinfunction "1_1") (pintype "passive"))
      (node (ref "U3") (pin "5") (pinfunction "SDA_5") (pintype "passive"))
    )
    (net (code "79") (name "Net-(U4-CANH)") (class "Default")
      (node (ref "P1") (pin "1") (pinfunction "1_1") (pintype "passive"))
      (node (ref "R8") (pin "1") (pinfunction "1_1") (pintype "passive"))
      (node (ref "U4") (pin "7") (pinfunction "CANH_7") (pintype "passive"))
    )
    (net (code "80") (name "Net-(U4-CANL)") (class "Default")
      (node (ref "P1") (pin "2") (pinfunction "2_2") (pintype "passive"))
      (node (ref "R8") (pin "2") (pinfunction "2_2") (pintype "passive"))
      (node (ref "U4") (pin "6") (pinfunction "CANL_6") (pintype "passive"))
    )
    (net (code "81") (name "Net-(U4-RXD)") (class "Default")
      (node (ref "JMP6") (pin "6") (pinfunction "6_6") (pintype "passive"))
      (node (ref "U4") (pin "4") (pinfunction "RXD_4") (pintype "passive"))
    )
    (net (code "82") (name "Net-(U4-TXD)") (class "Default")
      (node (ref "JMP6") (pin "5") (pinfunction "5_5") (pintype "passive"))
      (node (ref "U4") (pin "1") (pinfunction "TXD_1") (pintype "passive"))
    )
    (net (code "83") (name "Net-(U6-CLK)") (class "Default")
      (node (ref "JMP5") (pin "8") (pinfunction "8_8") (pintype "passive"))
      (node (ref "U6") (pin "6") (pinfunction "CLK_6") (pintype "passive"))
    )
    (net (code "84") (name "Net-(U6-DI)") (class "Default")
      (node (ref "JMP5") (pin "6") (pinfunction "6_6") (pintype "passive"))
      (node (ref "U6") (pin "5") (pinfunction "DI_5") (pintype "passive"))
    )
    (net (code "85") (name "Net-(U6-DO)") (class "Default")
      (node (ref "JMP5") (pin "4") (pinfunction "4_4") (pintype "passive"))
      (node (ref "U6") (pin "2") (pinfunction "DO_2") (pintype "passive"))
    )
    (net (code "86") (name "Net-(U6-~{CS})") (class "Default")
      (node (ref "JMP5") (pin "2") (pinfunction "2_2") (pintype "passive"))
      (node (ref "R6") (pin "1") (pinfunction "1_1") (pintype "passive"))
      (node (ref "U6") (pin "1") (pinfunction "~{CS}_1") (pintype "passive"))
    )
    (net (code "87") (name "Net-(USB2-D+)") (class "Default")
      (node (ref "R5") (pin "1") (pinfunction "1_1") (pintype "passive"))
      (node (ref "R9") (pin "1") (pinfunction "1_1") (pintype "passive"))
      (node (ref "USB2") (pin "3") (pinfunction "D+_3") (pintype "passive"))
    )
    (net (code "88") (name "Net-(USB2-D-)") (class "Default")
      (node (ref "R7") (pin "1") (pinfunction "1_1") (pintype "passive"))
      (node (ref "USB2") (pin "2") (pinfunction "D-_2") (pintype "passive"))
    )
    (net (code "89") (name "VDD") (class "Default")
      (node (ref "C1") (pin "2") (pinfunction "2_2") (pintype "passive"))
      (node (ref "C10") (pin "2") (pinfunction "2_2") (pintype "passive"))
      (node (ref "C13") (pin "2") (pinfunction "2_2") (pintype "passive"))
      (node (ref "C2") (pin "2") (pinfunction "2_2") (pintype "passive"))
      (node (ref "C3") (pin "2") (pinfunction "2_2") (pintype "passive"))
      (node (ref "C4") (pin "1") (pinfunction "1_1") (pintype "passive"))
      (node (ref "D2") (pin "A") (pinfunction "A_A") (pintype "passive"))
      (node (ref "D3") (pin "A") (pinfunction "A_A") (pintype "passive"))
      (node (ref "J1") (pin "1") (pinfunction "1_1") (pintype "passive"))
      (node (ref "J1") (pin "2") (pinfunction "2_2") (pintype "passive"))
      (node (ref "JMP3") (pin "1") (pinfunction "1_1") (pintype "passive"))
      (node (ref "L1") (pin "2") (pinfunction "2_2") (pintype "passive"))
      (node (ref "P3") (pin "24") (pinfunction "24_24") (pintype "passive"))
      (node (ref "P4") (pin "2") (pinfunction "2_2") (pintype "passive"))
      (node (ref "P5") (pin "1") (pinfunction "1_1") (pintype "passive"))
      (node (ref "R1") (pin "2") (pinfunction "2_2") (pintype "passive"))
      (node (ref "R10") (pin "2") (pinfunction "2_2") (pintype "passive"))
      (node (ref "R14") (pin "2") (pinfunction "2_2") (pintype "passive"))
      (node (ref "R15") (pin "2") (pinfunction "2_2") (pintype "passive"))
      (node (ref "R18") (pin "2") (pinfunction "2_2") (pintype "passive"))
      (node (ref "R2") (pin "2") (pinfunction "2_2") (pintype "passive"))
      (node (ref "R3") (pin "2") (pinfunction "2_2") (pintype "passive"))
      (node (ref "R4") (pin "2") (pinfunction "2_2") (pintype "passive"))
      (node (ref "R5") (pin "2") (pinfunction "2_2") (pintype "passive"))
      (node (ref "R6") (pin "2") (pinfunction "2_2") (pintype "passive"))
      (node (ref "U1") (pin "16") (pinfunction "VCC_16") (pintype "passive"))
      (node (ref "U1") (pin "4") (pinfunction "V3_4") (pintype "passive"))
      (node (ref "U3") (pin "8") (pinfunction "VCC_8") (pintype "passive"))
      (node (ref "U4") (pin "3") (pinfunction "VDD_3") (pintype "passive"))
      (node (ref "U6") (pin "3") (pinfunction "~{WP}_3") (pintype "passive"))
      (node (ref "U6") (pin "7") (pinfunction "~{HOLD}_7") (pintype "passive"))
      (node (ref "U6") (pin "8") (pinfunction "VCC_8") (pintype "passive"))
    )
    (net (code "90") (name "VDDA") (class "Default")
      (node (ref "C11") (pin "2") (pinfunction "2_2") (pintype "passive"))
      (node (ref "L2") (pin "2") (pinfunction "2_2") (pintype "passive"))
      (node (ref "U5") (pin "13") (pinfunction "VDDA_13") (pintype "passive"))
    )
    (net (code "91") (name "VDD_MCU") (class "Default")
      (node (ref "C12") (pin "1") (pinfunction "1_1") (pintype "passive"))
      (node (ref "C14") (pin "1") (pinfunction "1_1") (pintype "passive"))
      (node (ref "C18") (pin "1") (pinfunction "1_1") (pintype "passive"))
      (node (ref "JMP3") (pin "2") (pinfunction "2_2") (pintype "passive"))
      (node (ref "JMP7") (pin "1") (pinfunction "1_1") (pintype "passive"))
      (node (ref "JMP8") (pin "1") (pinfunction "1_1") (pintype "passive"))
      (node (ref "L2") (pin "1") (pinfunction "1_1") (pintype "passive"))
      (node (ref "U5") (pin "32") (pinfunction "VDD_32") (pintype "passive"))
      (node (ref "U5") (pin "48") (pinfunction "VDD_USB_48") (pintype "passive"))
      (node (ref "U5") (pin "64") (pinfunction "VDD_64") (pintype "passive"))
    )
    (net (code "92") (name "unconnected-(J1-Pad3)") (class "Default")
      (node (ref "J1") (pin "3") (pinfunction "3_3") (pintype "passive+no_connect"))
    )
    (net (code "93") (name "unconnected-(J1-Pad5)") (class "Default")
      (node (ref "J1") (pin "5") (pinfunction "5_5") (pintype "passive+no_connect"))
    )
    (net (code "94") (name "unconnected-(J1-Pad11)") (class "Default")
      (node (ref "J1") (pin "11") (pinfunction "11_11") (pintype "passive+no_connect"))
    )
    (net (code "95") (name "unconnected-(J1-Pad13)") (class "Default")
      (node (ref "J1") (pin "13") (pinfunction "13_13") (pintype "passive+no_connect"))
    )
    (net (code "96") (name "unconnected-(J1-Pad17)") (class "Default")
      (node (ref "J1") (pin "17") (pinfunction "17_17") (pintype "passive+no_connect"))
    )
    (net (code "97") (name "unconnected-(J1-Pad19)") (class "Default")
      (node (ref "J1") (pin "19") (pinfunction "19_19") (pintype "passive+no_connect"))
    )
    (net (code "98") (name "unconnected-(U1-CTS#-Pad9)") (class "Default")
      (node (ref "U1") (pin "9") (pinfunction "CTS#_9") (pintype "passive"))
    )
    (net (code "99") (name "unconnected-(U1-DCD#-Pad12)") (class "Default")
      (node (ref "U1") (pin "12") (pinfunction "DCD#_12") (pintype "passive"))
    )
    (net (code "100") (name "unconnected-(U1-DSR#-Pad10)") (class "Default")
      (node (ref "U1") (pin "10") (pinfunction "DSR#_10") (pintype "passive"))
    )
    (net (code "101") (name "unconnected-(U1-DTR#-Pad13)") (class "Default")
      (node (ref "U1") (pin "13") (pinfunction "DTR#_13") (pintype "passive"))
    )
    (net (code "102") (name "unconnected-(U1-NC-Pad7)") (class "Default")
      (node (ref "U1") (pin "7") (pinfunction "NC_7") (pintype "passive"))
    )
    (net (code "103") (name "unconnected-(U1-OUT#-Pad8)") (class "Default")
      (node (ref "U1") (pin "8") (pinfunction "OUT#_8") (pintype "passive"))
    )
    (net (code "104") (name "unconnected-(U1-RI#-Pad11)") (class "Default")
      (node (ref "U1") (pin "11") (pinfunction "RI#_11") (pintype "passive"))
    )
    (net (code "105") (name "unconnected-(U1-RS232-Pad15)") (class "Default")
      (node (ref "U1") (pin "15") (pinfunction "RS232_15") (pintype "passive"))
    )
    (net (code "106") (name "unconnected-(U1-RTS#-Pad14)") (class "Default")
      (node (ref "U1") (pin "14") (pinfunction "RTS#_14") (pintype "passive"))
    )
    (net (code "107") (name "unconnected-(U4-Vref-Pad5)") (class "Default")
      (node (ref "U4") (pin "5") (pinfunction "Vref_5") (pintype "passive+no_connect"))
    )
    (net (code "108") (name "unconnected-(USB1-ID-Pad4)") (class "Default")
      (node (ref "USB1") (pin "4") (pinfunction "ID_4") (pintype "passive+no_connect"))
    )
    (net (code "109") (name "unconnected-(USB2-ID-Pad4)") (class "Default")
      (node (ref "USB2") (pin "4") (pinfunction "ID_4") (pintype "passive+no_connect"))
    )
  )
)
